# S2C.net
KiCad netlist of a schematic drawn in Altium Designer
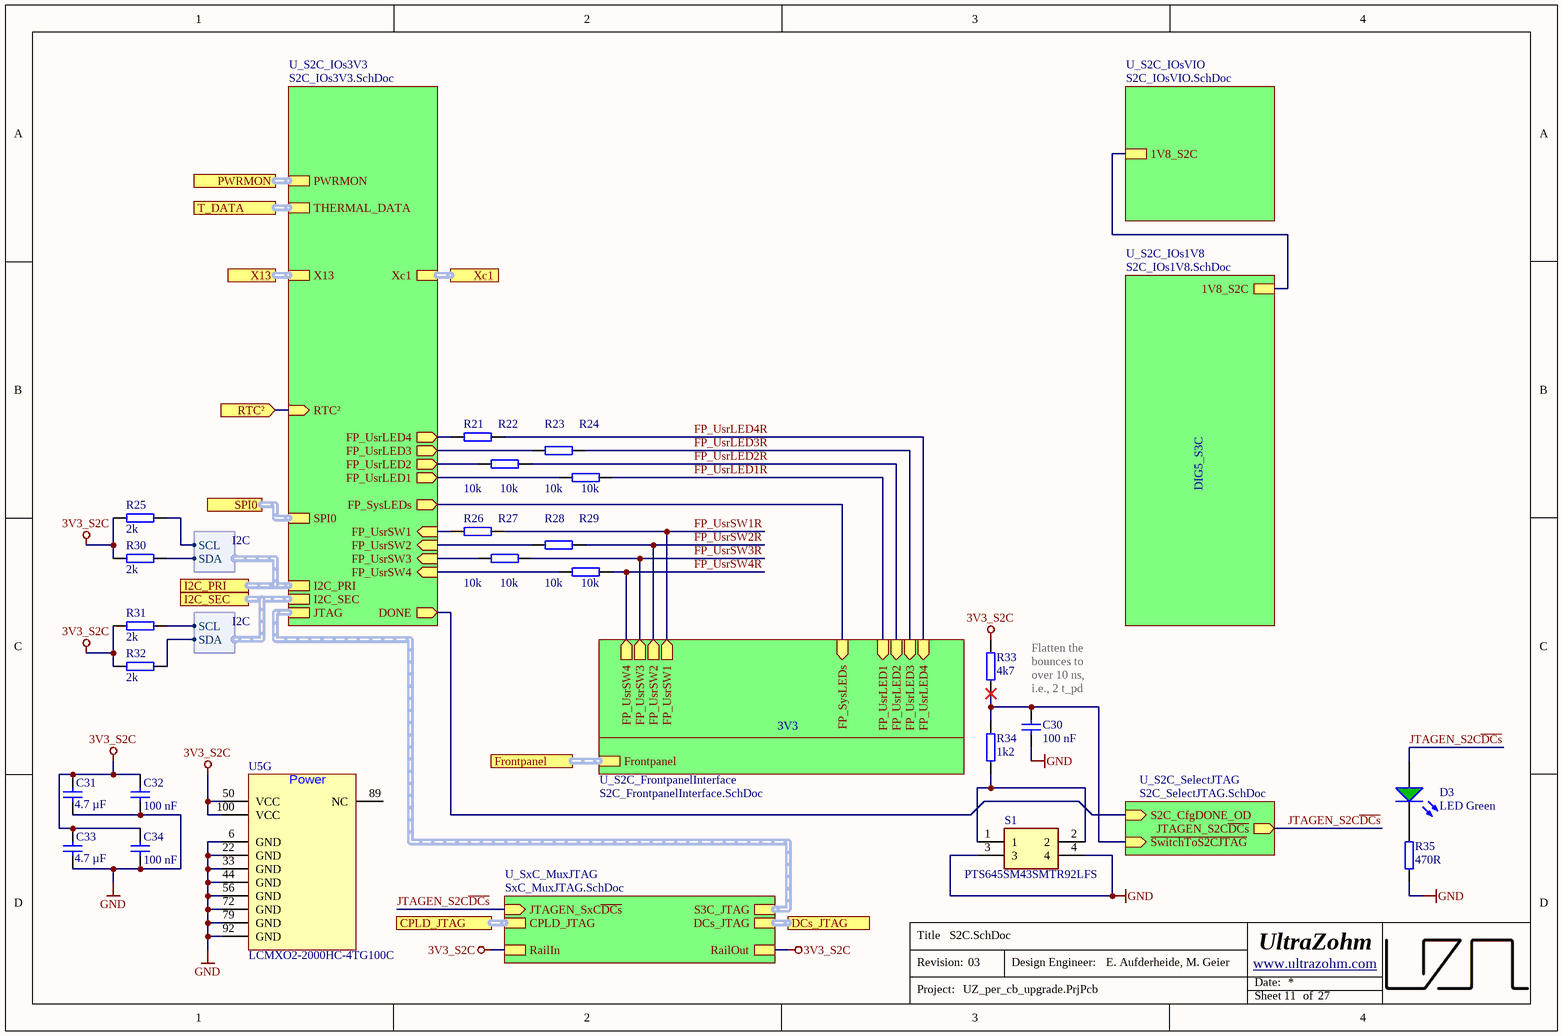
[diagram p0: S2C.SchDoc]

(export (version "E")
  (design (tool "Eeschema 10.0.6"))
  (components
    (comp (ref "C30")
      (value "100 nF")
      (footprint "C_0603_TE")
      (description "Generic capacitor")
      (fields
        (field (name "MANUFACTURER PART NUMBER") "UZgen_C_0603_100nF_50V_X7R")
        (field (name "MANUFACTURER") "UZgen")
        (field (name "CREATED FROM") "AGeiger")
      )
      (libsource (lib "user") (part "CAP-NP"))
    )
    (comp (ref "C31")
      (value "4.7 µF")
      (footprint "C_0603_TE")
      (description "Generic capacitor")
      (fields
        (field (name "MANUFACTURER PART NUMBER") "UZgen_C_0603_4.7uF_16V_X5R")
        (field (name "MANUFACTURER") "UZgen")
        (field (name "CREATED FROM") "MGeier")
      )
      (libsource (lib "user") (part "CAP-NP"))
    )
    (comp (ref "C32")
      (value "100 nF")
      (footprint "C_0603_TE")
      (description "Generic capacitor")
      (fields
        (field (name "TOLERANCE") "10 %")
        (field (name "VOLTAGE") "50 V")
        (field (name "CREATED FROM") "AGeiger")
      )
      (libsource (lib "user") (part "CAP-NP"))
    )
    (comp (ref "C33")
      (value "4.7 µF")
      (footprint "C_0603_TE")
      (description "Generic capacitor")
      (fields
        (field (name "MANUFACTURER PART NUMBER") "UZgen_C_0603_4.7uF_16V_X5R")
        (field (name "MANUFACTURER") "UZgen")
        (field (name "CREATED FROM") "MGeier")
      )
      (libsource (lib "user") (part "CAP-NP"))
    )
    (comp (ref "C34")
      (value "100 nF")
      (footprint "C_0603_TE")
      (description "Generic capacitor")
      (fields
        (field (name "TOLERANCE") "10 %")
        (field (name "VOLTAGE") "50 V")
        (field (name "CREATED FROM") "AGeiger")
      )
      (libsource (lib "user") (part "CAP-NP"))
    )
    (comp (ref "D3")
      (value "LED Green")
      (footprint "WL-SMCW_0603")
      (description "Standard LEDs - SMD 0603 green")
      (fields
        (field (name "MANUFACTURER PART NUMBER") "UZgen_LED_0603_Green")
        (field (name "MANUFACTURER") "UZgen")
        (field (name "CREATED FROM") "UZgenTool")
      )
      (libsource (lib "user") (part "LED_Green"))
    )
    (comp (ref "R21")
      (value "10k")
      (footprint "R_0603_TE")
      (description "Generic resistor")
      (fields
        (field (name "TOLERANCE") "1 %")
        (field (name "MANUFACTURER PART NUMBER") "UZgen_R_0603_10k")
        (field (name "CREATED FROM") "AGeiger")
      )
      (libsource (lib "user") (part "RES"))
    )
    (comp (ref "R22")
      (value "10k")
      (footprint "R_0603_TE")
      (description "Generic resistor")
      (fields
        (field (name "TOLERANCE") "1 %")
        (field (name "MANUFACTURER PART NUMBER") "UZgen_R_0603_10k")
        (field (name "CREATED FROM") "AGeiger")
      )
      (libsource (lib "user") (part "RES"))
    )
    (comp (ref "R23")
      (value "10k")
      (footprint "R_0603_TE")
      (description "Generic resistor")
      (fields
        (field (name "TOLERANCE") "1 %")
        (field (name "MANUFACTURER PART NUMBER") "UZgen_R_0603_10k")
        (field (name "CREATED FROM") "AGeiger")
      )
      (libsource (lib "user") (part "RES"))
    )
    (comp (ref "R24")
      (value "10k")
      (footprint "R_0603_TE")
      (description "Generic resistor")
      (fields
        (field (name "TOLERANCE") "1 %")
        (field (name "MANUFACTURER PART NUMBER") "UZgen_R_0603_10k")
        (field (name "CREATED FROM") "AGeiger")
      )
      (libsource (lib "user") (part "RES"))
    )
    (comp (ref "R25")
      (value "2k")
      (footprint "R_0603_TE")
      (description "Generic resistor")
      (fields
        (field (name "TOLERANCE") "1 %")
        (field (name "MANUFACTURER PART NUMBER") "UZgen_R_0603_2k")
        (field (name "CREATED FROM") "UZgenTool")
      )
      (libsource (lib "user") (part "RES"))
    )
    (comp (ref "R26")
      (value "10k")
      (footprint "R_0603_TE")
      (description "Generic resistor")
      (fields
        (field (name "TOLERANCE") "1 %")
        (field (name "MANUFACTURER PART NUMBER") "UZgen_R_0603_10k")
        (field (name "CREATED FROM") "AGeiger")
      )
      (libsource (lib "user") (part "RES"))
    )
    (comp (ref "R27")
      (value "10k")
      (footprint "R_0603_TE")
      (description "Generic resistor")
      (fields
        (field (name "TOLERANCE") "1 %")
        (field (name "MANUFACTURER PART NUMBER") "UZgen_R_0603_10k")
        (field (name "CREATED FROM") "AGeiger")
      )
      (libsource (lib "user") (part "RES"))
    )
    (comp (ref "R28")
      (value "10k")
      (footprint "R_0603_TE")
      (description "Generic resistor")
      (fields
        (field (name "TOLERANCE") "1 %")
        (field (name "MANUFACTURER PART NUMBER") "UZgen_R_0603_10k")
        (field (name "CREATED FROM") "AGeiger")
      )
      (libsource (lib "user") (part "RES"))
    )
    (comp (ref "R29")
      (value "10k")
      (footprint "R_0603_TE")
      (description "Generic resistor")
      (fields
        (field (name "TOLERANCE") "1 %")
        (field (name "MANUFACTURER PART NUMBER") "UZgen_R_0603_10k")
        (field (name "CREATED FROM") "AGeiger")
      )
      (libsource (lib "user") (part "RES"))
    )
    (comp (ref "R30")
      (value "2k")
      (footprint "R_0603_TE")
      (description "Generic resistor")
      (fields
        (field (name "TOLERANCE") "1 %")
        (field (name "MANUFACTURER PART NUMBER") "UZgen_R_0603_2k")
        (field (name "CREATED FROM") "UZgenTool")
      )
      (libsource (lib "user") (part "RES"))
    )
    (comp (ref "R31")
      (value "2k")
      (footprint "R_0603_TE")
      (description "Generic resistor")
      (fields
        (field (name "TOLERANCE") "1 %")
        (field (name "MANUFACTURER PART NUMBER") "UZgen_R_0603_2k")
        (field (name "CREATED FROM") "UZgenTool")
      )
      (libsource (lib "user") (part "RES"))
    )
    (comp (ref "R32")
      (value "2k")
      (footprint "R_0603_TE")
      (description "Generic resistor")
      (fields
        (field (name "TOLERANCE") "1 %")
        (field (name "MANUFACTURER PART NUMBER") "UZgen_R_0603_2k")
        (field (name "CREATED FROM") "UZgenTool")
      )
      (libsource (lib "user") (part "RES"))
    )
    (comp (ref "R33")
      (value "4k7")
      (footprint "R_0603_TE")
      (description "Generic resistor")
      (fields
        (field (name "MANUFACTURER PART NUMBER") "UZgen_R_0603_4k7")
        (field (name "MANUFACTURER") "UZgen")
        (field (name "CREATED FROM") "UZgenTool")
      )
      (libsource (lib "user") (part "RES"))
    )
    (comp (ref "R34")
      (value "1k2")
      (footprint "R_0603_TE")
      (description "Generic resistor")
      (fields
        (field (name "MANUFACTURER PART NUMBER") "UZgen_R_0603_1k2")
        (field (name "MANUFACTURER") "UZgen")
        (field (name "CREATED FROM") "UZgenTool")
      )
      (libsource (lib "user") (part "RES"))
    )
    (comp (ref "R35")
      (value "470R")
      (footprint "R_0603_TE")
      (description "Generic resistor")
      (fields
        (field (name "MANUFACTURER PART NUMBER") "UZgen_R_0603_470R")
        (field (name "MANUFACTURER") "UZgen")
        (field (name "CREATED FROM") "UZgenTool")
      )
      (libsource (lib "user") (part "RES"))
    )
    (comp (ref "S1")
      (value "PTS645SM43SMTR92LFS")
      (footprint "PTS645_SMT")
      (description "50mA SPST 160gf 12V SMD-4P,6x6mm Tactile Switches ROHS")
      (fields
        (field (name "MOUSER PART NUMBER") "611-PTS645SM43SMTR92")
        (field (name "MANUFACTURER") "C&K COMPONENTS")
        (field (name "CREATED FROM") "AGeiger")
      )
      (libsource (lib "user") (part "PTS645SM43SMTR92LFS"))
    )
    (comp (ref "U5")
      (value "LCMXO2-2000HC-4TG100C")
      (footprint "QFP50P1600X1600X160-100N")
      (description "TQFP-100(14x14) Programmable Logic Device (CPLDs/FPGAs) ROHS")
      (fields
        (field (name "MANUFACTURER") "Lattice")
        (field (name "LCSC PART NUMBER") "C1521632")
        (field (name "CREATED FROM") "FRosner")
      )
      (libsource (lib "user") (part "LCMXO2-2000"))
    )
  )
  (nets
    (net (code "15") (name "/FP_UsrLED1") (class "Default")
      (node (ref "R24") (pin "1") (pinfunction "1_1") (pintype "passive"))
    )
    (net (code "16") (name "/FP_UsrLED1R") (class "Default")
      (node (ref "R24") (pin "2") (pinfunction "2_2") (pintype "passive"))
    )
    (net (code "17") (name "/FP_UsrLED2") (class "Default")
      (node (ref "R22") (pin "1") (pinfunction "1_1") (pintype "passive"))
    )
    (net (code "18") (name "/FP_UsrLED2R") (class "Default")
      (node (ref "R22") (pin "2") (pinfunction "2_2") (pintype "passive"))
    )
    (net (code "19") (name "/FP_UsrLED3") (class "Default")
      (node (ref "R23") (pin "1") (pinfunction "1_1") (pintype "passive"))
    )
    (net (code "20") (name "/FP_UsrLED3R") (class "Default")
      (node (ref "R23") (pin "2") (pinfunction "2_2") (pintype "passive"))
    )
    (net (code "21") (name "/FP_UsrLED4") (class "Default")
      (node (ref "R21") (pin "1") (pinfunction "1_1") (pintype "passive"))
    )
    (net (code "22") (name "/FP_UsrLED4R") (class "Default")
      (node (ref "R21") (pin "2") (pinfunction "2_2") (pintype "passive"))
    )
    (net (code "23") (name "/FP_UsrSW1") (class "Default")
      (node (ref "R26") (pin "1") (pinfunction "1_1") (pintype "passive"))
    )
    (net (code "24") (name "/FP_UsrSW1R") (class "Default")
      (node (ref "R26") (pin "2") (pinfunction "2_2") (pintype "passive"))
    )
    (net (code "25") (name "/FP_UsrSW2") (class "Default")
      (node (ref "R28") (pin "1") (pinfunction "1_1") (pintype "passive"))
    )
    (net (code "26") (name "/FP_UsrSW2R") (class "Default")
      (node (ref "R28") (pin "2") (pinfunction "2_2") (pintype "passive"))
    )
    (net (code "27") (name "/FP_UsrSW3") (class "Default")
      (node (ref "R27") (pin "1") (pinfunction "1_1") (pintype "passive"))
    )
    (net (code "28") (name "/FP_UsrSW3R") (class "Default")
      (node (ref "R27") (pin "2") (pinfunction "2_2") (pintype "passive"))
    )
    (net (code "29") (name "/FP_UsrSW4") (class "Default")
      (node (ref "R29") (pin "1") (pinfunction "1_1") (pintype "passive"))
    )
    (net (code "30") (name "/FP_UsrSW4R") (class "Default")
      (node (ref "R29") (pin "2") (pinfunction "2_2") (pintype "passive"))
    )
    (net (code "32") (name "/JTAGEN_S2C~{DCs}") (class "Default")
      (node (ref "D3") (pin "2") (pinfunction "A_2") (pintype "passive"))
    )
    (net (code "41") (name "/~{SwitchToS2CJTAG}") (class "Default")
      (node (ref "C30") (pin "2") (pinfunction "2_2") (pintype "passive"))
      (node (ref "R33") (pin "1") (pinfunction "1_1") (pintype "passive"))
      (node (ref "R34") (pin "2") (pinfunction "2_2") (pintype "passive"))
    )
    (net (code "42") (name "3V3_S2C") (class "Default")
      (node (ref "C31") (pin "1") (pinfunction "1_1") (pintype "passive"))
      (node (ref "C32") (pin "2") (pinfunction "2_2") (pintype "passive"))
      (node (ref "C33") (pin "1") (pinfunction "1_1") (pintype "passive"))
      (node (ref "C34") (pin "2") (pinfunction "2_2") (pintype "passive"))
      (node (ref "R25") (pin "2") (pinfunction "2_2") (pintype "passive"))
      (node (ref "R30") (pin "2") (pinfunction "2_2") (pintype "passive"))
      (node (ref "R31") (pin "2") (pinfunction "2_2") (pintype "passive"))
      (node (ref "R32") (pin "2") (pinfunction "2_2") (pintype "passive"))
      (node (ref "R33") (pin "2") (pinfunction "2_2") (pintype "passive"))
      (node (ref "U5") (pin "100") (pinfunction "VCC_100") (pintype "power_in"))
      (node (ref "U5") (pin "50") (pinfunction "VCC_50") (pintype "power_in"))
    )
    (net (code "43") (name "GND") (class "Default")
      (node (ref "C30") (pin "1") (pinfunction "1_1") (pintype "passive"))
      (node (ref "C31") (pin "2") (pinfunction "2_2") (pintype "passive"))
      (node (ref "C32") (pin "1") (pinfunction "1_1") (pintype "passive"))
      (node (ref "C33") (pin "2") (pinfunction "2_2") (pintype "passive"))
      (node (ref "C34") (pin "1") (pinfunction "1_1") (pintype "passive"))
      (node (ref "R35") (pin "2") (pinfunction "2_2") (pintype "passive"))
      (node (ref "S1") (pin "3") (pinfunction "3_3") (pintype "passive"))
      (node (ref "S1") (pin "4") (pinfunction "4_4") (pintype "passive"))
      (node (ref "U5") (pin "22") (pinfunction "GND_22") (pintype "power_in"))
      (node (ref "U5") (pin "33") (pinfunction "GND_33") (pintype "power_in"))
      (node (ref "U5") (pin "44") (pinfunction "GND_44") (pintype "power_in"))
      (node (ref "U5") (pin "56") (pinfunction "GND_56") (pintype "power_in"))
      (node (ref "U5") (pin "6") (pinfunction "GND_6") (pintype "power_in"))
      (node (ref "U5") (pin "72") (pinfunction "GND_72") (pintype "power_in"))
      (node (ref "U5") (pin "79") (pinfunction "GND_79") (pintype "power_in"))
      (node (ref "U5") (pin "92") (pinfunction "GND_92") (pintype "power_in"))
    )
    (net (code "44") (name "Net-(D3-K)") (class "Default")
      (node (ref "D3") (pin "1") (pinfunction "K_1") (pintype "passive"))
      (node (ref "R35") (pin "1") (pinfunction "1_1") (pintype "passive"))
    )
    (net (code "45") (name "Net-(R34-Pad1)") (class "Default")
      (node (ref "R34") (pin "1") (pinfunction "1_1") (pintype "passive"))
      (node (ref "S1") (pin "1") (pinfunction "1_1") (pintype "passive"))
      (node (ref "S1") (pin "2") (pinfunction "2_2") (pintype "passive"))
    )
    (net (code "46") (name "unconnected-(R25-Pad1)") (class "Default")
      (node (ref "R25") (pin "1") (pinfunction "1_1") (pintype "passive"))
    )
    (net (code "47") (name "unconnected-(R30-Pad1)") (class "Default")
      (node (ref "R30") (pin "1") (pinfunction "1_1") (pintype "passive"))
    )
    (net (code "48") (name "unconnected-(R31-Pad1)") (class "Default")
      (node (ref "R31") (pin "1") (pinfunction "1_1") (pintype "passive"))
    )
    (net (code "49") (name "unconnected-(R32-Pad1)") (class "Default")
      (node (ref "R32") (pin "1") (pinfunction "1_1") (pintype "passive"))
    )
    (net (code "50") (name "unconnected-(U5G-NC-Pad89)") (class "Default")
      (node (ref "U5") (pin "89") (pinfunction "NC_89") (pintype "passive"))
    )
  )
)
